# Kasli_BP_Adapter.net
KiCad netlist of a schematic drawn in Altium Designer
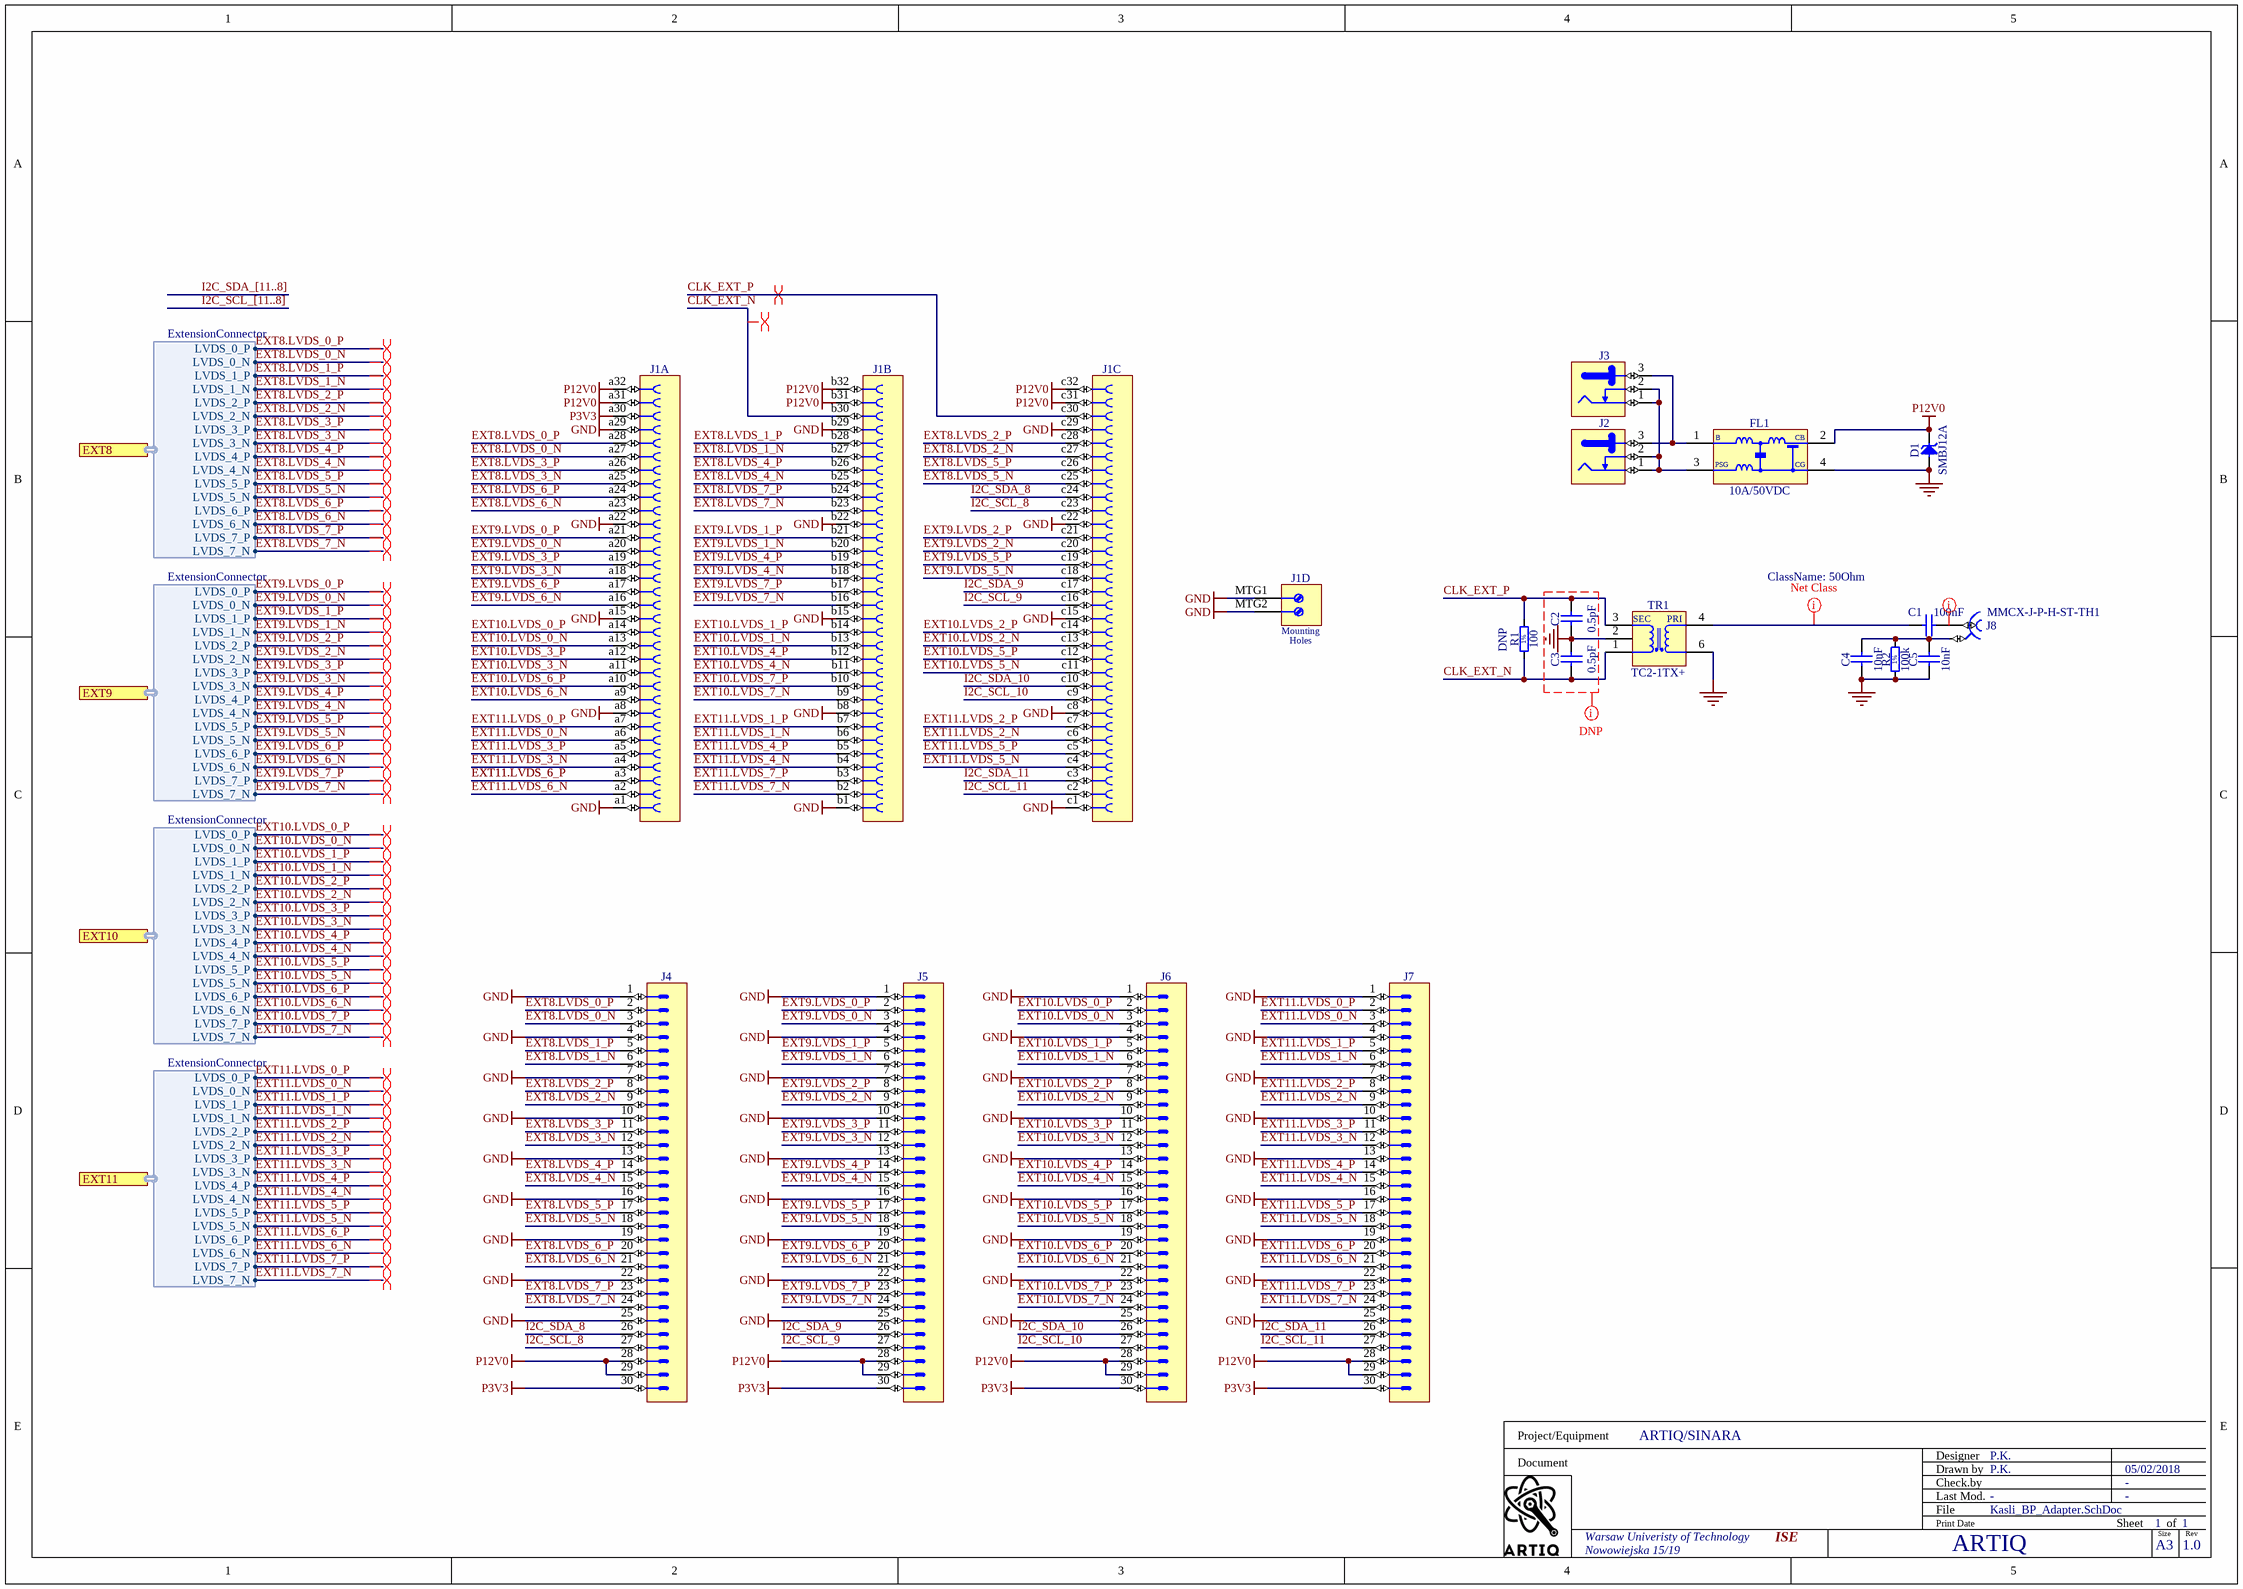
[diagram p0: Kasli_BP_Adapter.SchDoc]

(export (version "E")
  (design (tool "Eeschema 10.0.6"))
  (components
    (comp (ref "C1")
      (value "100nF")
      (footprint "CAPC0603X33N")
      (description "Non-polarised capacitor")
      (fields
        (field (name "PART NUMBER") "CC0201_100NF_6.3V_10%_X5R")
        (field (name "VOLTAGE") "6.3V")
        (field (name "AUTHOR") "CERN DEM JLC")
      )
      (libsource (lib "Capacitors") (part "Capacitor - non polarized"))
    )
    (comp (ref "C2")
      (value "0.5pF")
      (footprint "CAPC1005X50N")
      (description "Non-polarised capacitor")
      (fields
        (field (name "PART NUMBER") "CC0402_0.5PF_25V_0.05PF_AVX_04023J0R5ABSTR")
        (field (name "VOLTAGE") "25V")
        (field (name "AUTHOR") "CERN DEM JLC")
      )
      (libsource (lib "Capacitors") (part "Capacitor - non polarized"))
    )
    (comp (ref "C3")
      (value "0.5pF")
      (footprint "CAPC1005X50N")
      (description "Non-polarised capacitor")
      (fields
        (field (name "PART NUMBER") "CC0402_0.5PF_25V_0.05PF_AVX_04023J0R5ABSTR")
        (field (name "VOLTAGE") "25V")
        (field (name "AUTHOR") "CERN DEM JLC")
      )
      (libsource (lib "Capacitors") (part "Capacitor - non polarized"))
    )
    (comp (ref "C4")
      (value "10nF")
      (footprint "CAPC1005X55N")
      (description "Non-polarised capacitor")
      (fields
        (field (name "PART NUMBER") "CC0402_10NF_16V_10%_X7R")
        (field (name "VOLTAGE") "16V")
        (field (name "AUTHOR") "CERN DEM JLC")
      )
      (libsource (lib "Capacitors") (part "Capacitor - non polarized"))
    )
    (comp (ref "C5")
      (value "10nF")
      (footprint "CAPC1005X55N")
      (description "Non-polarised capacitor")
      (fields
        (field (name "PART NUMBER") "CC0402_10NF_16V_10%_X7R")
        (field (name "VOLTAGE") "16V")
        (field (name "AUTHOR") "CERN DEM JLC")
      )
      (libsource (lib "Capacitors") (part "Capacitor - non polarized"))
    )
    (comp (ref "D1")
      (value "SMBJ12A")
      (footprint "DIOM5336X265N")
      (description "Zener Diode")
      (fields
        (field (name "VOLTAGE") "12V")
        (field (name "POWER") "600W")
        (field (name "AUTHOR") "CERN DEM JLC")
      )
      (libsource (lib "ICs And Semiconductors") (part "Diode Zener"))
    )
    (comp (ref "FL1")
      (value "10A/50VDC")
      (footprint "FIL_MURATA_BNX02")
      (description "Block Type EMIFIL (LC Combined)")
      (fields
        (field (name "PART NUMBER") "FIL_MURATA_BNX022-01L")
        (field (name "MANUFACTURER") "MURATA")
        (field (name "AUTHOR") "CERN DEM JLC")
      )
      (libsource (lib "Inductors & Transformers") (part "FIL_MURATA_BNX02"))
    )
    (comp (ref "J1")
      (value "DIN 41612 Type R")
      (footprint "HARTING_09 73 296 6801")
      (description "Connector 96abc Female (3x32)")
      (fields
        (field (name "PART NUMBER") "HARTING_09 73 296 6801")
        (field (name "MANUFACTURER") "HARTING")
        (field (name "AUTHOR") "CERN DEM JLC")
      )
      (libsource (lib "Connectors") (part "Connector 96abc Female (3x32)"))
    )
    (comp (ref "J2")
      (value "Jack")
      (footprint "SWITCHCRAFT_L712RA")
      (description "24V /3. 5A, 2.1mm Diameter Pin, SMD DC Power Supply Connector With  Break Contact")
      (fields
        (field (name "PART NUMBER") "SWITCHCRAFT_712RA")
        (field (name "MANUFACTURER") "SWITCHCRAFT")
        (field (name "AUTHOR") "GK")
      )
      (libsource (lib "LIBRARY_SCH") (part "CON_DC_5A_THT_RA"))
    )
    (comp (ref "J3")
      (value "Jack")
      (footprint "SWITCHCRAFT_L712RA")
      (description "24V /3. 5A, 2.1mm Diameter Pin, SMD DC Power Supply Connector With  Break Contact")
      (fields
        (field (name "PART NUMBER") "SWITCHCRAFT_712RA")
        (field (name "MANUFACTURER") "SWITCHCRAFT")
        (field (name "AUTHOR") "GK")
      )
      (libsource (lib "LIBRARY_SCH") (part "CON_DC_5A_THT_RA"))
    )
    (comp (ref "J4")
      (value "~")
      (footprint "3M_N2530-6002RB")
      (description "Connector 30 Male")
      (fields
        (field (name "PART NUMBER") "3M_N2530-6002RB")
        (field (name "MANUFACTURER") "3M")
        (field (name "AUTHOR") "CERN DEM JLC")
      )
      (libsource (lib "Connectors") (part "Connector 30 Male"))
    )
    (comp (ref "J5")
      (value "~")
      (footprint "3M_N2530-6002RB")
      (description "Connector 30 Male")
      (fields
        (field (name "PART NUMBER") "3M_N2530-6002RB")
        (field (name "MANUFACTURER") "3M")
        (field (name "AUTHOR") "CERN DEM JLC")
      )
      (libsource (lib "Connectors") (part "Connector 30 Male"))
    )
    (comp (ref "J6")
      (value "~")
      (footprint "3M_N2530-6002RB")
      (description "Connector 30 Male")
      (fields
        (field (name "PART NUMBER") "3M_N2530-6002RB")
        (field (name "MANUFACTURER") "3M")
        (field (name "AUTHOR") "CERN DEM JLC")
      )
      (libsource (lib "Connectors") (part "Connector 30 Male"))
    )
    (comp (ref "J7")
      (value "~")
      (footprint "3M_N2530-6002RB")
      (description "Connector 30 Male")
      (fields
        (field (name "PART NUMBER") "3M_N2530-6002RB")
        (field (name "MANUFACTURER") "3M")
        (field (name "AUTHOR") "CERN DEM JLC")
      )
      (libsource (lib "Connectors") (part "Connector 30 Male"))
    )
    (comp (ref "J8")
      (value "MMCX-J-P-H-ST-TH1")
      (footprint "SAMTEC_MMCX-J-P-H-ST-TH1")
      (fields
        (field (name "PART NUMBER") "SAMTEC_MMCX-J-P-H-ST-TH1")
        (field (name "MANUFACTURER") "SAMTEC")
        (field (name "AUTHOR") "CERN DEM JLC")
      )
      (libsource (lib "Connectors") (part "Coax_1Female_1Shield"))
    )
    (comp (ref "R1")
      (value "100")
      (footprint "RESC1005X40N")
      (description "Resistor - 1%")
      (fields
        (field (name "PART NUMBER") "R0402_100R_1%_0.0625W_100PPM")
        (field (name "POWER") "0.0625W")
        (field (name "AUTHOR") "CERN DEM JLC")
      )
      (libsource (lib "Resistors") (part "Resistor - 1%"))
    )
    (comp (ref "R2")
      (value "100k")
      (footprint "RESC1005X40N")
      (description "Resistor - 1%")
      (fields
        (field (name "PART NUMBER") "R0402_100K_1%_0.0625W_100PPM")
        (field (name "MANUFACTURER") "GENERIC")
        (field (name "AUTHOR") "CERN DEM JLC")
      )
      (libsource (lib "Resistors") (part "Resistor - 1%"))
    )
    (comp (ref "TR1")
      (value "TC2-1TX+")
      (footprint "XFMR_MINI-CIRCUITS_AT1521")
      (description "50 Ohm 3 to 300MHz RF Transformers")
      (fields (field (name "MANUFACTURER") "MINI-CIRCUITS"))
      (libsource (lib "Schlib1") (part "XFMR_MINI-CIRCUITS_TC2-1TX+"))
    )
  )
  (nets
    (net (code "2") (name "/CLK_EXT_N") (class "Default")
      (node (ref "C3") (pin "1") (pinfunction "1_1") (pintype "passive"))
      (node (ref "J1") (pin "b30") (pinfunction "b30_b30") (pintype "bidirectional"))
      (node (ref "R1") (pin "1") (pinfunction "1_1") (pintype "passive"))
      (node (ref "TR1") (pin "1") (pinfunction "SDOT_1") (pintype "passive"))
    )
    (net (code "3") (name "/CLK_EXT_P") (class "Default")
      (node (ref "C2") (pin "2") (pinfunction "2_2") (pintype "passive"))
      (node (ref "J1") (pin "c30") (pinfunction "c30_c30") (pintype "bidirectional"))
      (node (ref "R1") (pin "2") (pinfunction "2_2") (pintype "passive"))
      (node (ref "TR1") (pin "3") (pinfunction "S_3") (pintype "passive"))
    )
    (net (code "4") (name "/EXT8.LVDS_0_N") (class "Default")
      (node (ref "J1") (pin "a27") (pinfunction "a27_a27") (pintype "bidirectional"))
      (node (ref "J4") (pin "3") (pinfunction "3_3") (pintype "bidirectional"))
    )
    (net (code "5") (name "/EXT8.LVDS_0_P") (class "Default")
      (node (ref "J1") (pin "a28") (pinfunction "a28_a28") (pintype "bidirectional"))
      (node (ref "J4") (pin "2") (pinfunction "2_2") (pintype "bidirectional"))
    )
    (net (code "6") (name "/EXT8.LVDS_1_N") (class "Default")
      (node (ref "J1") (pin "b27") (pinfunction "b27_b27") (pintype "bidirectional"))
      (node (ref "J4") (pin "6") (pinfunction "6_6") (pintype "bidirectional"))
    )
    (net (code "7") (name "/EXT8.LVDS_1_P") (class "Default")
      (node (ref "J1") (pin "b28") (pinfunction "b28_b28") (pintype "bidirectional"))
      (node (ref "J4") (pin "5") (pinfunction "5_5") (pintype "bidirectional"))
    )
    (net (code "8") (name "/EXT8.LVDS_2_N") (class "Default")
      (node (ref "J1") (pin "c27") (pinfunction "c27_c27") (pintype "bidirectional"))
      (node (ref "J4") (pin "9") (pinfunction "9_9") (pintype "bidirectional"))
    )
    (net (code "9") (name "/EXT8.LVDS_2_P") (class "Default")
      (node (ref "J1") (pin "c28") (pinfunction "c28_c28") (pintype "bidirectional"))
      (node (ref "J4") (pin "8") (pinfunction "8_8") (pintype "bidirectional"))
    )
    (net (code "10") (name "/EXT8.LVDS_3_N") (class "Default")
      (node (ref "J1") (pin "a25") (pinfunction "a25_a25") (pintype "bidirectional"))
      (node (ref "J4") (pin "12") (pinfunction "12_12") (pintype "bidirectional"))
    )
    (net (code "11") (name "/EXT8.LVDS_3_P") (class "Default")
      (node (ref "J1") (pin "a26") (pinfunction "a26_a26") (pintype "bidirectional"))
      (node (ref "J4") (pin "11") (pinfunction "11_11") (pintype "bidirectional"))
    )
    (net (code "12") (name "/EXT8.LVDS_4_N") (class "Default")
      (node (ref "J1") (pin "b25") (pinfunction "b25_b25") (pintype "bidirectional"))
      (node (ref "J4") (pin "15") (pinfunction "15_15") (pintype "bidirectional"))
    )
    (net (code "13") (name "/EXT8.LVDS_4_P") (class "Default")
      (node (ref "J1") (pin "b26") (pinfunction "b26_b26") (pintype "bidirectional"))
      (node (ref "J4") (pin "14") (pinfunction "14_14") (pintype "bidirectional"))
    )
    (net (code "14") (name "/EXT8.LVDS_5_N") (class "Default")
      (node (ref "J1") (pin "c25") (pinfunction "c25_c25") (pintype "bidirectional"))
      (node (ref "J4") (pin "18") (pinfunction "18_18") (pintype "bidirectional"))
    )
    (net (code "15") (name "/EXT8.LVDS_5_P") (class "Default")
      (node (ref "J1") (pin "c26") (pinfunction "c26_c26") (pintype "bidirectional"))
      (node (ref "J4") (pin "17") (pinfunction "17_17") (pintype "bidirectional"))
    )
    (net (code "16") (name "/EXT8.LVDS_6_N") (class "Default")
      (node (ref "J1") (pin "a23") (pinfunction "a23_a23") (pintype "bidirectional"))
      (node (ref "J4") (pin "21") (pinfunction "21_21") (pintype "bidirectional"))
    )
    (net (code "17") (name "/EXT8.LVDS_6_P") (class "Default")
      (node (ref "J1") (pin "a24") (pinfunction "a24_a24") (pintype "bidirectional"))
      (node (ref "J4") (pin "20") (pinfunction "20_20") (pintype "bidirectional"))
    )
    (net (code "18") (name "/EXT8.LVDS_7_N") (class "Default")
      (node (ref "J1") (pin "b23") (pinfunction "b23_b23") (pintype "bidirectional"))
      (node (ref "J4") (pin "24") (pinfunction "24_24") (pintype "bidirectional"))
    )
    (net (code "19") (name "/EXT8.LVDS_7_P") (class "Default")
      (node (ref "J1") (pin "b24") (pinfunction "b24_b24") (pintype "bidirectional"))
      (node (ref "J4") (pin "23") (pinfunction "23_23") (pintype "bidirectional"))
    )
    (net (code "20") (name "/EXT9.LVDS_0_N") (class "Default")
      (node (ref "J1") (pin "a20") (pinfunction "a20_a20") (pintype "bidirectional"))
      (node (ref "J5") (pin "3") (pinfunction "3_3") (pintype "bidirectional"))
    )
    (net (code "21") (name "/EXT9.LVDS_0_P") (class "Default")
      (node (ref "J1") (pin "a21") (pinfunction "a21_a21") (pintype "bidirectional"))
      (node (ref "J5") (pin "2") (pinfunction "2_2") (pintype "bidirectional"))
    )
    (net (code "22") (name "/EXT9.LVDS_1_N") (class "Default")
      (node (ref "J1") (pin "b20") (pinfunction "b20_b20") (pintype "bidirectional"))
      (node (ref "J5") (pin "6") (pinfunction "6_6") (pintype "bidirectional"))
    )
    (net (code "23") (name "/EXT9.LVDS_1_P") (class "Default")
      (node (ref "J1") (pin "b21") (pinfunction "b21_b21") (pintype "bidirectional"))
      (node (ref "J5") (pin "5") (pinfunction "5_5") (pintype "bidirectional"))
    )
    (net (code "24") (name "/EXT9.LVDS_2_N") (class "Default")
      (node (ref "J1") (pin "c20") (pinfunction "c20_c20") (pintype "bidirectional"))
      (node (ref "J5") (pin "9") (pinfunction "9_9") (pintype "bidirectional"))
    )
    (net (code "25") (name "/EXT9.LVDS_2_P") (class "Default")
      (node (ref "J1") (pin "c21") (pinfunction "c21_c21") (pintype "bidirectional"))
      (node (ref "J5") (pin "8") (pinfunction "8_8") (pintype "bidirectional"))
    )
    (net (code "26") (name "/EXT9.LVDS_3_N") (class "Default")
      (node (ref "J1") (pin "a18") (pinfunction "a18_a18") (pintype "bidirectional"))
      (node (ref "J5") (pin "12") (pinfunction "12_12") (pintype "bidirectional"))
    )
    (net (code "27") (name "/EXT9.LVDS_3_P") (class "Default")
      (node (ref "J1") (pin "a19") (pinfunction "a19_a19") (pintype "bidirectional"))
      (node (ref "J5") (pin "11") (pinfunction "11_11") (pintype "bidirectional"))
    )
    (net (code "28") (name "/EXT9.LVDS_4_N") (class "Default")
      (node (ref "J1") (pin "b18") (pinfunction "b18_b18") (pintype "bidirectional"))
      (node (ref "J5") (pin "15") (pinfunction "15_15") (pintype "bidirectional"))
    )
    (net (code "29") (name "/EXT9.LVDS_4_P") (class "Default")
      (node (ref "J1") (pin "b19") (pinfunction "b19_b19") (pintype "bidirectional"))
      (node (ref "J5") (pin "14") (pinfunction "14_14") (pintype "bidirectional"))
    )
    (net (code "30") (name "/EXT9.LVDS_5_N") (class "Default")
      (node (ref "J1") (pin "c18") (pinfunction "c18_c18") (pintype "bidirectional"))
      (node (ref "J5") (pin "18") (pinfunction "18_18") (pintype "bidirectional"))
    )
    (net (code "31") (name "/EXT9.LVDS_5_P") (class "Default")
      (node (ref "J1") (pin "c19") (pinfunction "c19_c19") (pintype "bidirectional"))
      (node (ref "J5") (pin "17") (pinfunction "17_17") (pintype "bidirectional"))
    )
    (net (code "32") (name "/EXT9.LVDS_6_N") (class "Default")
      (node (ref "J1") (pin "a16") (pinfunction "a16_a16") (pintype "bidirectional"))
      (node (ref "J5") (pin "21") (pinfunction "21_21") (pintype "bidirectional"))
    )
    (net (code "33") (name "/EXT9.LVDS_6_P") (class "Default")
      (node (ref "J1") (pin "a17") (pinfunction "a17_a17") (pintype "bidirectional"))
      (node (ref "J5") (pin "20") (pinfunction "20_20") (pintype "bidirectional"))
    )
    (net (code "34") (name "/EXT9.LVDS_7_N") (class "Default")
      (node (ref "J1") (pin "b16") (pinfunction "b16_b16") (pintype "bidirectional"))
      (node (ref "J5") (pin "24") (pinfunction "24_24") (pintype "bidirectional"))
    )
    (net (code "35") (name "/EXT9.LVDS_7_P") (class "Default")
      (node (ref "J1") (pin "b17") (pinfunction "b17_b17") (pintype "bidirectional"))
      (node (ref "J5") (pin "23") (pinfunction "23_23") (pintype "bidirectional"))
    )
    (net (code "36") (name "/EXT10.LVDS_0_N") (class "Default")
      (node (ref "J1") (pin "a13") (pinfunction "a13_a13") (pintype "bidirectional"))
      (node (ref "J6") (pin "3") (pinfunction "3_3") (pintype "bidirectional"))
    )
    (net (code "37") (name "/EXT10.LVDS_0_P") (class "Default")
      (node (ref "J1") (pin "a14") (pinfunction "a14_a14") (pintype "bidirectional"))
      (node (ref "J6") (pin "2") (pinfunction "2_2") (pintype "bidirectional"))
    )
    (net (code "38") (name "/EXT10.LVDS_1_N") (class "Default")
      (node (ref "J1") (pin "b13") (pinfunction "b13_b13") (pintype "bidirectional"))
      (node (ref "J6") (pin "6") (pinfunction "6_6") (pintype "bidirectional"))
    )
    (net (code "39") (name "/EXT10.LVDS_1_P") (class "Default")
      (node (ref "J1") (pin "b14") (pinfunction "b14_b14") (pintype "bidirectional"))
      (node (ref "J6") (pin "5") (pinfunction "5_5") (pintype "bidirectional"))
    )
    (net (code "40") (name "/EXT10.LVDS_2_N") (class "Default")
      (node (ref "J1") (pin "c13") (pinfunction "c13_c13") (pintype "bidirectional"))
      (node (ref "J6") (pin "9") (pinfunction "9_9") (pintype "bidirectional"))
    )
    (net (code "41") (name "/EXT10.LVDS_2_P") (class "Default")
      (node (ref "J1") (pin "c14") (pinfunction "c14_c14") (pintype "bidirectional"))
      (node (ref "J6") (pin "8") (pinfunction "8_8") (pintype "bidirectional"))
    )
    (net (code "42") (name "/EXT10.LVDS_3_N") (class "Default")
      (node (ref "J1") (pin "a11") (pinfunction "a11_a11") (pintype "bidirectional"))
      (node (ref "J6") (pin "12") (pinfunction "12_12") (pintype "bidirectional"))
    )
    (net (code "43") (name "/EXT10.LVDS_3_P") (class "Default")
      (node (ref "J1") (pin "a12") (pinfunction "a12_a12") (pintype "bidirectional"))
      (node (ref "J6") (pin "11") (pinfunction "11_11") (pintype "bidirectional"))
    )
    (net (code "44") (name "/EXT10.LVDS_4_N") (class "Default")
      (node (ref "J1") (pin "b11") (pinfunction "b11_b11") (pintype "bidirectional"))
      (node (ref "J6") (pin "15") (pinfunction "15_15") (pintype "bidirectional"))
    )
    (net (code "45") (name "/EXT10.LVDS_4_P") (class "Default")
      (node (ref "J1") (pin "b12") (pinfunction "b12_b12") (pintype "bidirectional"))
      (node (ref "J6") (pin "14") (pinfunction "14_14") (pintype "bidirectional"))
    )
    (net (code "46") (name "/EXT10.LVDS_5_N") (class "Default")
      (node (ref "J1") (pin "c11") (pinfunction "c11_c11") (pintype "bidirectional"))
      (node (ref "J6") (pin "18") (pinfunction "18_18") (pintype "bidirectional"))
    )
    (net (code "47") (name "/EXT10.LVDS_5_P") (class "Default")
      (node (ref "J1") (pin "c12") (pinfunction "c12_c12") (pintype "bidirectional"))
      (node (ref "J6") (pin "17") (pinfunction "17_17") (pintype "bidirectional"))
    )
    (net (code "48") (name "/EXT10.LVDS_6_N") (class "Default")
      (node (ref "J1") (pin "a9") (pinfunction "a9_a9") (pintype "bidirectional"))
      (node (ref "J6") (pin "21") (pinfunction "21_21") (pintype "bidirectional"))
    )
    (net (code "49") (name "/EXT10.LVDS_6_P") (class "Default")
      (node (ref "J1") (pin "a10") (pinfunction "a10_a10") (pintype "bidirectional"))
      (node (ref "J6") (pin "20") (pinfunction "20_20") (pintype "bidirectional"))
    )
    (net (code "50") (name "/EXT10.LVDS_7_N") (class "Default")
      (node (ref "J1") (pin "b9") (pinfunction "b9_b9") (pintype "bidirectional"))
      (node (ref "J6") (pin "24") (pinfunction "24_24") (pintype "bidirectional"))
    )
    (net (code "51") (name "/EXT10.LVDS_7_P") (class "Default")
      (node (ref "J1") (pin "b10") (pinfunction "b10_b10") (pintype "bidirectional"))
      (node (ref "J6") (pin "23") (pinfunction "23_23") (pintype "bidirectional"))
    )
    (net (code "52") (name "/EXT11.LVDS_0_N") (class "Default")
      (node (ref "J1") (pin "a6") (pinfunction "a6_a6") (pintype "bidirectional"))
      (node (ref "J7") (pin "3") (pinfunction "3_3") (pintype "bidirectional"))
    )
    (net (code "53") (name "/EXT11.LVDS_0_P") (class "Default")
      (node (ref "J1") (pin "a7") (pinfunction "a7_a7") (pintype "bidirectional"))
      (node (ref "J7") (pin "2") (pinfunction "2_2") (pintype "bidirectional"))
    )
    (net (code "54") (name "/EXT11.LVDS_1_N") (class "Default")
      (node (ref "J1") (pin "b6") (pinfunction "b6_b6") (pintype "bidirectional"))
      (node (ref "J7") (pin "6") (pinfunction "6_6") (pintype "bidirectional"))
    )
    (net (code "55") (name "/EXT11.LVDS_1_P") (class "Default")
      (node (ref "J1") (pin "b7") (pinfunction "b7_b7") (pintype "bidirectional"))
      (node (ref "J7") (pin "5") (pinfunction "5_5") (pintype "bidirectional"))
    )
    (net (code "56") (name "/EXT11.LVDS_2_N") (class "Default")
      (node (ref "J1") (pin "c6") (pinfunction "c6_c6") (pintype "bidirectional"))
      (node (ref "J7") (pin "9") (pinfunction "9_9") (pintype "bidirectional"))
    )
    (net (code "57") (name "/EXT11.LVDS_2_P") (class "Default")
      (node (ref "J1") (pin "c7") (pinfunction "c7_c7") (pintype "bidirectional"))
      (node (ref "J7") (pin "8") (pinfunction "8_8") (pintype "bidirectional"))
    )
    (net (code "58") (name "/EXT11.LVDS_3_N") (class "Default")
      (node (ref "J1") (pin "a4") (pinfunction "a4_a4") (pintype "bidirectional"))
      (node (ref "J7") (pin "12") (pinfunction "12_12") (pintype "bidirectional"))
    )
    (net (code "59") (name "/EXT11.LVDS_3_P") (class "Default")
      (node (ref "J1") (pin "a5") (pinfunction "a5_a5") (pintype "bidirectional"))
      (node (ref "J7") (pin "11") (pinfunction "11_11") (pintype "bidirectional"))
    )
    (net (code "60") (name "/EXT11.LVDS_4_N") (class "Default")
      (node (ref "J1") (pin "b4") (pinfunction "b4_b4") (pintype "bidirectional"))
      (node (ref "J7") (pin "15") (pinfunction "15_15") (pintype "bidirectional"))
    )
    (net (code "61") (name "/EXT11.LVDS_4_P") (class "Default")
      (node (ref "J1") (pin "b5") (pinfunction "b5_b5") (pintype "bidirectional"))
      (node (ref "J7") (pin "14") (pinfunction "14_14") (pintype "bidirectional"))
    )
    (net (code "62") (name "/EXT11.LVDS_5_N") (class "Default")
      (node (ref "J1") (pin "c4") (pinfunction "c4_c4") (pintype "bidirectional"))
      (node (ref "J7") (pin "18") (pinfunction "18_18") (pintype "bidirectional"))
    )
    (net (code "63") (name "/EXT11.LVDS_5_P") (class "Default")
      (node (ref "J1") (pin "c5") (pinfunction "c5_c5") (pintype "bidirectional"))
      (node (ref "J7") (pin "17") (pinfunction "17_17") (pintype "bidirectional"))
    )
    (net (code "64") (name "/EXT11.LVDS_6_N") (class "Default")
      (node (ref "J1") (pin "a2") (pinfunction "a2_a2") (pintype "bidirectional"))
      (node (ref "J7") (pin "21") (pinfunction "21_21") (pintype "bidirectional"))
    )
    (net (code "65") (name "/EXT11.LVDS_6_P") (class "Default")
      (node (ref "J1") (pin "a3") (pinfunction "a3_a3") (pintype "bidirectional"))
      (node (ref "J7") (pin "20") (pinfunction "20_20") (pintype "bidirectional"))
    )
    (net (code "66") (name "/EXT11.LVDS_7_N") (class "Default")
      (node (ref "J1") (pin "b2") (pinfunction "b2_b2") (pintype "bidirectional"))
      (node (ref "J7") (pin "24") (pinfunction "24_24") (pintype "bidirectional"))
    )
    (net (code "67") (name "/EXT11.LVDS_7_P") (class "Default")
      (node (ref "J1") (pin "b3") (pinfunction "b3_b3") (pintype "bidirectional"))
      (node (ref "J7") (pin "23") (pinfunction "23_23") (pintype "bidirectional"))
    )
    (net (code "68") (name "/I2C_SCL_8") (class "Default")
      (node (ref "J1") (pin "c23") (pinfunction "c23_c23") (pintype "bidirectional"))
      (node (ref "J4") (pin "27") (pinfunction "27_27") (pintype "bidirectional"))
    )
    (net (code "69") (name "/I2C_SCL_9") (class "Default")
      (node (ref "J1") (pin "c16") (pinfunction "c16_c16") (pintype "bidirectional"))
      (node (ref "J5") (pin "27") (pinfunction "27_27") (pintype "bidirectional"))
    )
    (net (code "70") (name "/I2C_SCL_10") (class "Default")
      (node (ref "J1") (pin "c9") (pinfunction "c9_c9") (pintype "bidirectional"))
      (node (ref "J6") (pin "27") (pinfunction "27_27") (pintype "bidirectional"))
    )
    (net (code "71") (name "/I2C_SCL_11") (class "Default")
      (node (ref "J1") (pin "c2") (pinfunction "c2_c2") (pintype "bidirectional"))
      (node (ref "J7") (pin "27") (pinfunction "27_27") (pintype "bidirectional"))
    )
    (net (code "73") (name "/I2C_SDA_8") (class "Default")
      (node (ref "J1") (pin "c24") (pinfunction "c24_c24") (pintype "bidirectional"))
      (node (ref "J4") (pin "26") (pinfunction "26_26") (pintype "bidirectional"))
    )
    (net (code "74") (name "/I2C_SDA_9") (class "Default")
      (node (ref "J1") (pin "c17") (pinfunction "c17_c17") (pintype "bidirectional"))
      (node (ref "J5") (pin "26") (pinfunction "26_26") (pintype "bidirectional"))
    )
    (net (code "75") (name "/I2C_SDA_10") (class "Default")
      (node (ref "J1") (pin "c10") (pinfunction "c10_c10") (pintype "bidirectional"))
      (node (ref "J6") (pin "26") (pinfunction "26_26") (pintype "bidirectional"))
    )
    (net (code "76") (name "/I2C_SDA_11") (class "Default")
      (node (ref "J1") (pin "c3") (pinfunction "c3_c3") (pintype "bidirectional"))
      (node (ref "J7") (pin "26") (pinfunction "26_26") (pintype "bidirectional"))
    )
    (net (code "79") (name "GND") (class "Default")
      (node (ref "C2") (pin "1") (pinfunction "1_1") (pintype "passive"))
      (node (ref "C3") (pin "2") (pinfunction "2_2") (pintype "passive"))
      (node (ref "C4") (pin "1") (pinfunction "1_1") (pintype "passive"))
      (node (ref "C5") (pin "1") (pinfunction "1_1") (pintype "passive"))
      (node (ref "D1") (pin "2") (pinfunction "A_2") (pintype "passive"))
      (node (ref "FL1") (pin "4") (pinfunction "CG_4") (pintype "passive"))
      (node (ref "J1") (pin "MTG1") (pinfunction "MTG1_MTG1") (pintype "passive"))
      (node (ref "J1") (pin "MTG2") (pinfunction "MTG2_MTG2") (pintype "passive"))
      (node (ref "J1") (pin "a1") (pinfunction "a1_a1") (pintype "bidirectional"))
      (node (ref "J1") (pin "a15") (pinfunction "a15_a15") (pintype "bidirectional"))
      (node (ref "J1") (pin "a22") (pinfunction "a22_a22") (pintype "bidirectional"))
      (node (ref "J1") (pin "a29") (pinfunction "a29_a29") (pintype "bidirectional"))
      (node (ref "J1") (pin "a8") (pinfunction "a8_a8") (pintype "bidirectional"))
      (node (ref "J1") (pin "b1") (pinfunction "b1_b1") (pintype "bidirectional"))
      (node (ref "J1") (pin "b15") (pinfunction "b15_b15") (pintype "bidirectional"))
      (node (ref "J1") (pin "b22") (pinfunction "b22_b22") (pintype "bidirectional"))
      (node (ref "J1") (pin "b29") (pinfunction "b29_b29") (pintype "bidirectional"))
      (node (ref "J1") (pin "b8") (pinfunction "b8_b8") (pintype "bidirectional"))
      (node (ref "J1") (pin "c1") (pinfunction "c1_c1") (pintype "bidirectional"))
      (node (ref "J1") (pin "c15") (pinfunction "c15_c15") (pintype "bidirectional"))
      (node (ref "J1") (pin "c22") (pinfunction "c22_c22") (pintype "bidirectional"))
      (node (ref "J1") (pin "c29") (pinfunction "c29_c29") (pintype "bidirectional"))
      (node (ref "J1") (pin "c8") (pinfunction "c8_c8") (pintype "bidirectional"))
      (node (ref "J4") (pin "1") (pinfunction "1_1") (pintype "bidirectional"))
      (node (ref "J4") (pin "10") (pinfunction "10_10") (pintype "bidirectional"))
      (node (ref "J4") (pin "13") (pinfunction "13_13") (pintype "bidirectional"))
      (node (ref "J4") (pin "16") (pinfunction "16_16") (pintype "bidirectional"))
      (node (ref "J4") (pin "19") (pinfunction "19_19") (pintype "bidirectional"))
      (node (ref "J4") (pin "22") (pinfunction "22_22") (pintype "bidirectional"))
      (node (ref "J4") (pin "25") (pinfunction "25_25") (pintype "bidirectional"))
      (node (ref "J4") (pin "4") (pinfunction "4_4") (pintype "bidirectional"))
      (node (ref "J4") (pin "7") (pinfunction "7_7") (pintype "bidirectional"))
      (node (ref "J5") (pin "1") (pinfunction "1_1") (pintype "bidirectional"))
      (node (ref "J5") (pin "10") (pinfunction "10_10") (pintype "bidirectional"))
      (node (ref "J5") (pin "13") (pinfunction "13_13") (pintype "bidirectional"))
      (node (ref "J5") (pin "16") (pinfunction "16_16") (pintype "bidirectional"))
      (node (ref "J5") (pin "19") (pinfunction "19_19") (pintype "bidirectional"))
      (node (ref "J5") (pin "22") (pinfunction "22_22") (pintype "bidirectional"))
      (node (ref "J5") (pin "25") (pinfunction "25_25") (pintype "bidirectional"))
      (node (ref "J5") (pin "4") (pinfunction "4_4") (pintype "bidirectional"))
      (node (ref "J5") (pin "7") (pinfunction "7_7") (pintype "bidirectional"))
      (node (ref "J6") (pin "1") (pinfunction "1_1") (pintype "bidirectional"))
      (node (ref "J6") (pin "10") (pinfunction "10_10") (pintype "bidirectional"))
      (node (ref "J6") (pin "13") (pinfunction "13_13") (pintype "bidirectional"))
      (node (ref "J6") (pin "16") (pinfunction "16_16") (pintype "bidirectional"))
      (node (ref "J6") (pin "19") (pinfunction "19_19") (pintype "bidirectional"))
      (node (ref "J6") (pin "22") (pinfunction "22_22") (pintype "bidirectional"))
      (node (ref "J6") (pin "25") (pinfunction "25_25") (pintype "bidirectional"))
      (node (ref "J6") (pin "4") (pinfunction "4_4") (pintype "bidirectional"))
      (node (ref "J6") (pin "7") (pinfunction "7_7") (pintype "bidirectional"))
      (node (ref "J7") (pin "1") (pinfunction "1_1") (pintype "bidirectional"))
      (node (ref "J7") (pin "10") (pinfunction "10_10") (pintype "bidirectional"))
      (node (ref "J7") (pin "13") (pinfunction "13_13") (pintype "bidirectional"))
      (node (ref "J7") (pin "16") (pinfunction "16_16") (pintype "bidirectional"))
      (node (ref "J7") (pin "19") (pinfunction "19_19") (pintype "bidirectional"))
      (node (ref "J7") (pin "22") (pinfunction "22_22") (pintype "bidirectional"))
      (node (ref "J7") (pin "25") (pinfunction "25_25") (pintype "bidirectional"))
      (node (ref "J7") (pin "4") (pinfunction "4_4") (pintype "bidirectional"))
      (node (ref "J7") (pin "7") (pinfunction "7_7") (pintype "bidirectional"))
      (node (ref "R2") (pin "1") (pinfunction "1_1") (pintype "passive"))
      (node (ref "TR1") (pin "2") (pinfunction "NU_2") (pintype "passive"))
      (node (ref "TR1") (pin "6") (pinfunction "PDOT_6") (pintype "passive"))
    )
    (net (code "80") (name "Net-(C1-Pad2)") (class "Default")
      (node (ref "C1") (pin "2") (pinfunction "2_2") (pintype "passive"))
      (node (ref "J8") (pin "1") (pinfunction "1_1") (pintype "bidirectional"))
    )
    (net (code "81") (name "Net-(C4-Pad2)") (class "Default")
      (node (ref "C4") (pin "2") (pinfunction "2_2") (pintype "passive"))
      (node (ref "C5") (pin "2") (pinfunction "2_2") (pintype "passive"))
      (node (ref "J8") (pin "2") (pinfunction "2_2") (pintype "bidirectional"))
      (node (ref "R2") (pin "2") (pinfunction "2_2") (pintype "passive"))
    )
    (net (code "82") (name "Net-(FL1-B)") (class "Default")
      (node (ref "FL1") (pin "1") (pinfunction "B_1") (pintype "passive"))
      (node (ref "J2") (pin "3") (pinfunction "3_3") (pintype "bidirectional"))
      (node (ref "J3") (pin "3") (pinfunction "3_3") (pintype "bidirectional"))
    )
    (net (code "83") (name "Net-(FL1-PSG)") (class "Default")
      (node (ref "FL1") (pin "3") (pinfunction "PSG_3") (pintype "passive"))
      (node (ref "J2") (pin "1") (pinfunction "1_1") (pintype "bidirectional"))
      (node (ref "J2") (pin "2") (pinfunction "2_2") (pintype "bidirectional"))
      (node (ref "J3") (pin "1") (pinfunction "1_1") (pintype "bidirectional"))
      (node (ref "J3") (pin "2") (pinfunction "2_2") (pintype "bidirectional"))
    )
    (net (code "84") (name "Net-(TR1-P)") (class "Default")
      (node (ref "C1") (pin "1") (pinfunction "1_1") (pintype "passive"))
      (node (ref "TR1") (pin "4") (pinfunction "P_4") (pintype "passive"))
    )
    (net (code "85") (name "P3V3") (class "Default")
      (node (ref "J1") (pin "a30") (pinfunction "a30_a30") (pintype "bidirectional"))
      (node (ref "J4") (pin "30") (pinfunction "30_30") (pintype "bidirectional"))
      (node (ref "J5") (pin "30") (pinfunction "30_30") (pintype "bidirectional"))
      (node (ref "J6") (pin "30") (pinfunction "30_30") (pintype "bidirectional"))
      (node (ref "J7") (pin "30") (pinfunction "30_30") (pintype "bidirectional"))
    )
    (net (code "86") (name "P12V0") (class "Default")
      (node (ref "D1") (pin "1") (pinfunction "C_1") (pintype "passive"))
      (node (ref "FL1") (pin "2") (pinfunction "CB_2") (pintype "passive"))
      (node (ref "J1") (pin "a31") (pinfunction "a31_a31") (pintype "bidirectional"))
      (node (ref "J1") (pin "a32") (pinfunction "a32_a32") (pintype "bidirectional"))
      (node (ref "J1") (pin "b31") (pinfunction "b31_b31") (pintype "bidirectional"))
      (node (ref "J1") (pin "b32") (pinfunction "b32_b32") (pintype "bidirectional"))
      (node (ref "J1") (pin "c31") (pinfunction "c31_c31") (pintype "bidirectional"))
      (node (ref "J1") (pin "c32") (pinfunction "c32_c32") (pintype "bidirectional"))
      (node (ref "J4") (pin "28") (pinfunction "28_28") (pintype "bidirectional"))
      (node (ref "J4") (pin "29") (pinfunction "29_29") (pintype "bidirectional"))
      (node (ref "J5") (pin "28") (pinfunction "28_28") (pintype "bidirectional"))
      (node (ref "J5") (pin "29") (pinfunction "29_29") (pintype "bidirectional"))
      (node (ref "J6") (pin "28") (pinfunction "28_28") (pintype "bidirectional"))
      (node (ref "J6") (pin "29") (pinfunction "29_29") (pintype "bidirectional"))
      (node (ref "J7") (pin "28") (pinfunction "28_28") (pintype "bidirectional"))
      (node (ref "J7") (pin "29") (pinfunction "29_29") (pintype "bidirectional"))
    )
  )
)
